# RingerPro.net
KiCad netlist of a schematic drawn in EAGLE
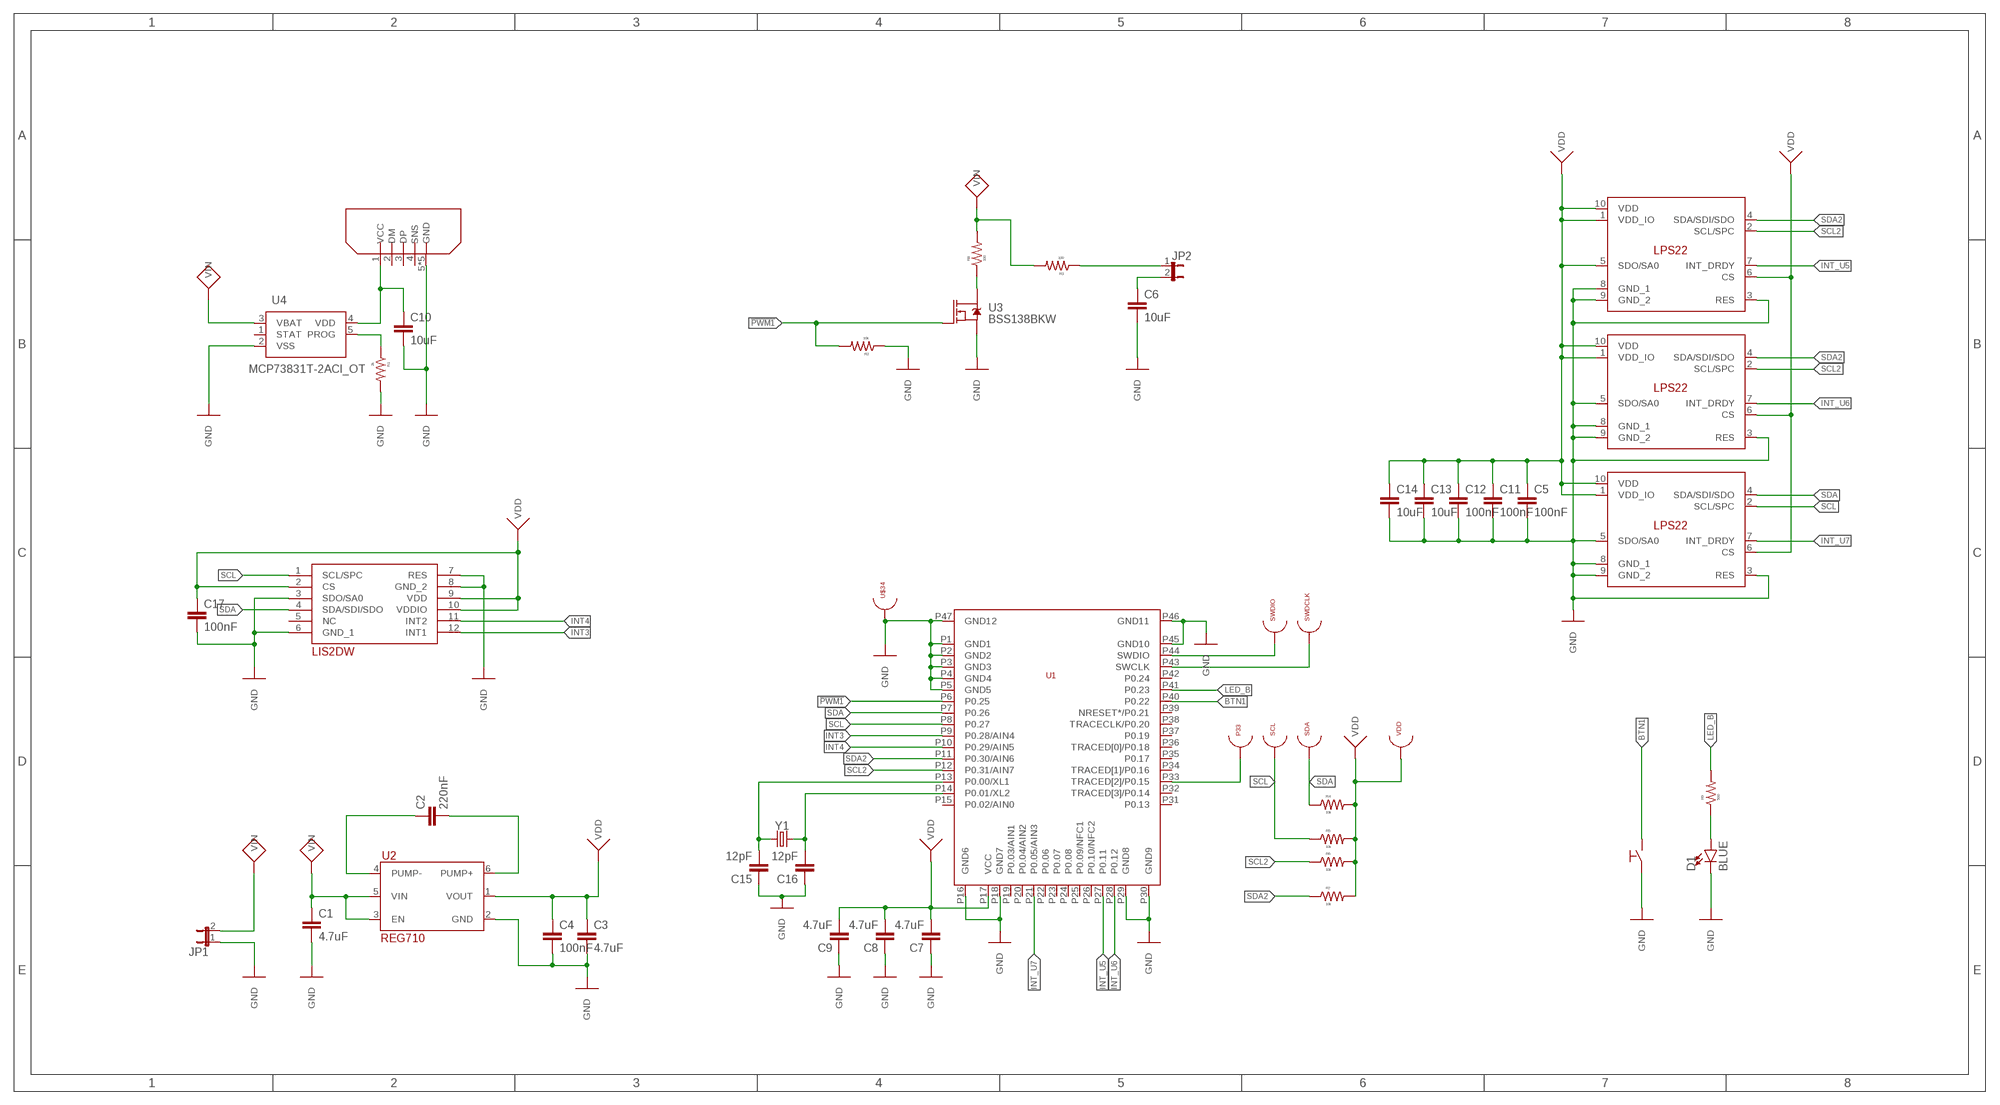
[diagram p0: schematic, sheet 1]

(export (version "E")
  (design (tool "Eeschema 10.0.6"))
  (components
    (comp (ref "C1")
      (value "4.7uF")
      (footprint "eagle-import:C0603")
      (libsource (lib "eagle-import") (part "CAPACITOR0603"))
    )
    (comp (ref "C2")
      (value "220nF")
      (footprint "eagle-import:C0603")
      (libsource (lib "eagle-import") (part "CAPACITOR0603"))
    )
    (comp (ref "C3")
      (value "4.7uF")
      (footprint "eagle-import:C0603")
      (libsource (lib "eagle-import") (part "CAPACITOR0603"))
    )
    (comp (ref "C4")
      (value "100nF")
      (footprint "eagle-import:C0603")
      (libsource (lib "eagle-import") (part "CAPACITOR0603"))
    )
    (comp (ref "C5")
      (value "100nF")
      (footprint "eagle-import:C0603")
      (libsource (lib "eagle-import") (part "CAPACITOR0603"))
    )
    (comp (ref "C6")
      (value "10uF")
      (footprint "eagle-import:C0603")
      (libsource (lib "eagle-import") (part "CAPACITOR0603"))
    )
    (comp (ref "C7")
      (value "4.7uF")
      (footprint "eagle-import:C0603")
      (libsource (lib "eagle-import") (part "CAPACITOR0603"))
    )
    (comp (ref "C8")
      (value "4.7uF")
      (footprint "eagle-import:C0603")
      (libsource (lib "eagle-import") (part "CAPACITOR0603"))
    )
    (comp (ref "C9")
      (value "4.7uF")
      (footprint "eagle-import:C0603")
      (libsource (lib "eagle-import") (part "CAPACITOR0603"))
    )
    (comp (ref "C10")
      (value "10uF")
      (footprint "eagle-import:C0603")
      (libsource (lib "eagle-import") (part "CAPACITOR0603"))
    )
    (comp (ref "C11")
      (value "100nF")
      (footprint "eagle-import:C0603")
      (libsource (lib "eagle-import") (part "CAPACITOR0603"))
    )
    (comp (ref "C12")
      (value "100nF")
      (footprint "eagle-import:C0603")
      (libsource (lib "eagle-import") (part "CAPACITOR0603"))
    )
    (comp (ref "C13")
      (value "10uF")
      (footprint "eagle-import:C0603")
      (libsource (lib "eagle-import") (part "CAPACITOR0603"))
    )
    (comp (ref "C14")
      (value "10uF")
      (footprint "eagle-import:C0603")
      (libsource (lib "eagle-import") (part "CAPACITOR0603"))
    )
    (comp (ref "C15")
      (value "12pF")
      (footprint "eagle-import:C0603")
      (libsource (lib "eagle-import") (part "CAPACITOR0603"))
    )
    (comp (ref "C16")
      (value "12pF")
      (footprint "eagle-import:C0603")
      (libsource (lib "eagle-import") (part "CAPACITOR0603"))
    )
    (comp (ref "C17")
      (value "100nF")
      (footprint "eagle-import:C0603")
      (libsource (lib "eagle-import") (part "CAPACITOR0603"))
    )
    (comp (ref "D1")
      (value "BLUE")
      (footprint "eagle-import:LED-0603")
      (libsource (lib "eagle-import") (part "LED-BLUE0603"))
    )
    (comp (ref "IC1")
      (value "LIS2DW12TR")
      (footprint "eagle-import:LGA-12")
      (fields (field (name "MOUSER_PART_NUMBER") "511-LIS2DW12TR"))
      (libsource (lib "eagle-import") (part "LIS2DW12TR"))
    )
    (comp (ref "JP1")
      (value "JP1E")
      (footprint "eagle-import:JP1")
      (libsource (lib "eagle-import") (part "JP1E"))
    )
    (comp (ref "JP2")
      (value "JP1E")
      (footprint "eagle-import:JP1")
      (libsource (lib "eagle-import") (part "JP1E"))
    )
    (comp (ref "P33")
      (value "TESTPOINT_22")
      (footprint "eagle-import:TESTPOINT_22")
      (libsource (lib "eagle-import") (part "TESTPOINT_22"))
    )
    (comp (ref "R1")
      (value "2k")
      (footprint "eagle-import:R0603")
      (libsource (lib "eagle-import") (part "RESISTOR0603"))
    )
    (comp (ref "R2")
      (value "10k")
      (footprint "eagle-import:R0603")
      (libsource (lib "eagle-import") (part "RESISTOR0603"))
    )
    (comp (ref "R3")
      (value "100")
      (footprint "eagle-import:R0603")
      (libsource (lib "eagle-import") (part "RESISTOR0603"))
    )
    (comp (ref "R4")
      (value "10k")
      (footprint "eagle-import:R0603")
      (libsource (lib "eagle-import") (part "RESISTOR0603"))
    )
    (comp (ref "R5")
      (value "10k")
      (footprint "eagle-import:R0603")
      (libsource (lib "eagle-import") (part "RESISTOR0603"))
    )
    (comp (ref "R6")
      (value "10k")
      (footprint "eagle-import:R0603")
      (libsource (lib "eagle-import") (part "RESISTOR0603"))
    )
    (comp (ref "R7")
      (value "10k")
      (footprint "eagle-import:R0603")
      (libsource (lib "eagle-import") (part "RESISTOR0603"))
    )
    (comp (ref "R8")
      (value "100")
      (footprint "eagle-import:R0603")
      (libsource (lib "eagle-import") (part "RESISTOR0603"))
    )
    (comp (ref "R9")
      (value "500")
      (footprint "eagle-import:R0603")
      (libsource (lib "eagle-import") (part "RESISTOR0603"))
    )
    (comp (ref "SCL")
      (value "TESTPOINT_22")
      (footprint "eagle-import:TESTPOINT_22")
      (libsource (lib "eagle-import") (part "TESTPOINT_22"))
    )
    (comp (ref "SDA")
      (value "TESTPOINT_22")
      (footprint "eagle-import:TESTPOINT_22")
      (libsource (lib "eagle-import") (part "TESTPOINT_22"))
    )
    (comp (ref "SPST1")
      (value "PTS526SK08")
      (footprint "eagle-import:PTS526SKG15SMTR2LFS")
      (libsource (lib "eagle-import") (part "PTS526SK08"))
    )
    (comp (ref "SWDCLK")
      (value "TESTPOINT_22")
      (footprint "eagle-import:TESTPOINT_22")
      (libsource (lib "eagle-import") (part "TESTPOINT_22"))
    )
    (comp (ref "SWDIO")
      (value "TESTPOINT_22")
      (footprint "eagle-import:TESTPOINT_22")
      (libsource (lib "eagle-import") (part "TESTPOINT_22"))
    )
    (comp (ref "U$23")
      (value "ZX80B5P")
      (footprint "eagle-import:ZX80B5P")
      (libsource (lib "eagle-import") (part "ZX80B5P"))
    )
    (comp (ref "U$34")
      (value "TESTPOINT_22")
      (footprint "eagle-import:TESTPOINT_22")
      (libsource (lib "eagle-import") (part "TESTPOINT_22"))
    )
    (comp (ref "U1")
      (value "BMD-300")
      (footprint "eagle-import:BMD-300")
      (libsource (lib "eagle-import") (part "BMD-300"))
    )
    (comp (ref "U2")
      (value "REG710")
      (footprint "eagle-import:SOT457")
      (libsource (lib "eagle-import") (part "REG710"))
    )
    (comp (ref "U3")
      (value "BSS138BKW")
      (footprint "eagle-import:SOT65P210X110-3N")
      (libsource (lib "eagle-import") (part "BSS138BKW"))
    )
    (comp (ref "U4")
      (value "MCP73831T-2ACI_OT")
      (footprint "eagle-import:SOT95P270X145-5N")
      (fields
        (field (name "MANUFACTURER_PART_NUMBER") "MCP73831T-2ACI/OT")
        (field (name "MOUSER_PART_NUMBER") "579-MCP73831T-2ACIOT")
      )
      (libsource (lib "eagle-import") (part "MCP73831T-2ACI_OT"))
    )
    (comp (ref "U5")
      (value "LPS22HBTR")
      (footprint "eagle-import:LPS22HDTR")
      (fields
        (field (name "MANUFACTURER_PART_NUMBER") "LPS22HDTR")
        (field (name "MOUSER_PART_NUMBER") "511-LPS22HDTR")
      )
      (libsource (lib "eagle-import") (part "LPS22HDTR"))
    )
    (comp (ref "U6")
      (value "LPS22HBTR")
      (footprint "eagle-import:LPS22HDTR")
      (fields
        (field (name "MANUFACTURER_PART_NUMBER") "LPS22HDTR")
        (field (name "MOUSER_PART_NUMBER") "511-LPS22HDTR")
      )
      (libsource (lib "eagle-import") (part "LPS22HDTR"))
    )
    (comp (ref "U7")
      (value "LPS22HBTR")
      (footprint "eagle-import:LPS22HDTR")
      (fields
        (field (name "MANUFACTURER_PART_NUMBER") "LPS22HDTR")
        (field (name "MOUSER_PART_NUMBER") "511-LPS22HDTR")
      )
      (libsource (lib "eagle-import") (part "LPS22HDTR"))
    )
    (comp (ref "VDD")
      (value "TESTPOINT_22")
      (footprint "eagle-import:TESTPOINT_22")
      (libsource (lib "eagle-import") (part "TESTPOINT_22"))
    )
    (comp (ref "Y1")
      (value "CRYSTALSMD-3.2X1.5")
      (footprint "eagle-import:CRYSTAL-SMD-3.2X1.5MM")
      (libsource (lib "eagle-import") (part "CRYSTALSMD-3.2X1.5"))
    )
  )
  (nets
    (net (code "1") (name "/~{PWM1}") (class "Default")
      (node (ref "R2") (pin "2") (pinfunction "2_2") (pintype "passive"))
      (node (ref "U1") (pin "P6") (pinfunction "P0.25_P6") (pintype "bidirectional"))
      (node (ref "U3") (pin "1") (pinfunction "G_1") (pintype "bidirectional"))
    )
    (net (code "2") (name "BTN1") (class "Default")
      (node (ref "SPST1") (pin "3") (pinfunction "P$2_3") (pintype "passive"))
      (node (ref "SPST1") (pin "4") (pinfunction "P$2_4") (pintype "passive"))
      (node (ref "U1") (pin "P40") (pinfunction "P0.22_P40") (pintype "bidirectional"))
    )
    (net (code "3") (name "GND") (class "Default")
      (node (ref "C1") (pin "2") (pinfunction "2_2") (pintype "passive"))
      (node (ref "C10") (pin "2") (pinfunction "2_2") (pintype "passive"))
      (node (ref "C11") (pin "2") (pinfunction "2_2") (pintype "passive"))
      (node (ref "C12") (pin "2") (pinfunction "2_2") (pintype "passive"))
      (node (ref "C13") (pin "2") (pinfunction "2_2") (pintype "passive"))
      (node (ref "C14") (pin "2") (pinfunction "2_2") (pintype "passive"))
      (node (ref "C15") (pin "1") (pinfunction "1_1") (pintype "passive"))
      (node (ref "C16") (pin "1") (pinfunction "1_1") (pintype "passive"))
      (node (ref "C17") (pin "2") (pinfunction "2_2") (pintype "passive"))
      (node (ref "C3") (pin "2") (pinfunction "2_2") (pintype "passive"))
      (node (ref "C4") (pin "2") (pinfunction "2_2") (pintype "passive"))
      (node (ref "C5") (pin "2") (pinfunction "2_2") (pintype "passive"))
      (node (ref "C6") (pin "2") (pinfunction "2_2") (pintype "passive"))
      (node (ref "C7") (pin "1") (pinfunction "1_1") (pintype "passive"))
      (node (ref "C8") (pin "1") (pinfunction "1_1") (pintype "passive"))
      (node (ref "C9") (pin "1") (pinfunction "1_1") (pintype "passive"))
      (node (ref "D1") (pin "C") (pinfunction "C_C") (pintype "passive"))
      (node (ref "IC1") (pin "3") (pinfunction "SDO/SA0_3") (pintype "bidirectional"))
      (node (ref "IC1") (pin "6") (pinfunction "GND_1_6") (pintype "bidirectional"))
      (node (ref "IC1") (pin "7") (pinfunction "RES_7") (pintype "bidirectional"))
      (node (ref "IC1") (pin "8") (pinfunction "GND_2_8") (pintype "bidirectional"))
      (node (ref "JP1") (pin "1") (pinfunction "1_1") (pintype "passive"))
      (node (ref "R1") (pin "2") (pinfunction "2_2") (pintype "passive"))
      (node (ref "R2") (pin "1") (pinfunction "1_1") (pintype "passive"))
      (node (ref "SPST1") (pin "1") (pinfunction "P$1_1") (pintype "passive"))
      (node (ref "SPST1") (pin "2") (pinfunction "P$1_2") (pintype "passive"))
      (node (ref "U$23") (pin "5") (pinfunction "GND_5") (pintype "bidirectional"))
      (node (ref "U$23") (pin "GND1") (pinfunction "GND_GND1") (pintype "bidirectional"))
      (node (ref "U$23") (pin "GND2") (pinfunction "GND_GND2") (pintype "bidirectional"))
      (node (ref "U$23") (pin "GND3") (pinfunction "GND_GND3") (pintype "bidirectional"))
      (node (ref "U$23") (pin "GND4") (pinfunction "GND_GND4") (pintype "bidirectional"))
      (node (ref "U$34") (pin "P$1") (pinfunction "P$1_P$1") (pintype "bidirectional"))
      (node (ref "U1") (pin "P1") (pinfunction "GND1_P1") (pintype "bidirectional"))
      (node (ref "U1") (pin "P16") (pinfunction "GND6_P16") (pintype "bidirectional"))
      (node (ref "U1") (pin "P18") (pinfunction "GND7_P18") (pintype "bidirectional"))
      (node (ref "U1") (pin "P2") (pinfunction "GND2_P2") (pintype "bidirectional"))
      (node (ref "U1") (pin "P29") (pinfunction "GND8_P29") (pintype "bidirectional"))
      (node (ref "U1") (pin "P3") (pinfunction "GND3_P3") (pintype "bidirectional"))
      (node (ref "U1") (pin "P30") (pinfunction "GND9_P30") (pintype "bidirectional"))
      (node (ref "U1") (pin "P4") (pinfunction "GND4_P4") (pintype "bidirectional"))
      (node (ref "U1") (pin "P45") (pinfunction "GND10_P45") (pintype "bidirectional"))
      (node (ref "U1") (pin "P46") (pinfunction "GND11_P46") (pintype "bidirectional"))
      (node (ref "U1") (pin "P47") (pinfunction "GND12_P47") (pintype "bidirectional"))
      (node (ref "U1") (pin "P5") (pinfunction "GND5_P5") (pintype "bidirectional"))
      (node (ref "U2") (pin "2") (pinfunction "GND_2") (pintype "bidirectional"))
      (node (ref "U3") (pin "2") (pinfunction "S_2") (pintype "bidirectional"))
      (node (ref "U4") (pin "2") (pinfunction "VSS_2") (pintype "bidirectional"))
      (node (ref "U5") (pin "3") (pinfunction "RES_3") (pintype "bidirectional"))
      (node (ref "U5") (pin "8") (pinfunction "GND_1_8") (pintype "bidirectional"))
      (node (ref "U5") (pin "9") (pinfunction "GND_2_9") (pintype "bidirectional"))
      (node (ref "U6") (pin "3") (pinfunction "RES_3") (pintype "bidirectional"))
      (node (ref "U6") (pin "5") (pinfunction "SDO/SA0_5") (pintype "bidirectional"))
      (node (ref "U6") (pin "8") (pinfunction "GND_1_8") (pintype "bidirectional"))
      (node (ref "U6") (pin "9") (pinfunction "GND_2_9") (pintype "bidirectional"))
      (node (ref "U7") (pin "3") (pinfunction "RES_3") (pintype "bidirectional"))
      (node (ref "U7") (pin "5") (pinfunction "SDO/SA0_5") (pintype "bidirectional"))
      (node (ref "U7") (pin "8") (pinfunction "GND_1_8") (pintype "bidirectional"))
      (node (ref "U7") (pin "9") (pinfunction "GND_2_9") (pintype "bidirectional"))
    )
    (net (code "4") (name "INT3") (class "Default")
      (node (ref "IC1") (pin "12") (pinfunction "INT1_12") (pintype "bidirectional"))
      (node (ref "U1") (pin "P9") (pinfunction "P0.28/AIN4_P9") (pintype "bidirectional"))
    )
    (net (code "5") (name "INT4") (class "Default")
      (node (ref "IC1") (pin "11") (pinfunction "INT2_11") (pintype "bidirectional"))
      (node (ref "U1") (pin "P10") (pinfunction "P0.29/AIN5_P10") (pintype "bidirectional"))
    )
    (net (code "6") (name "INT_U5") (class "Default")
      (node (ref "U1") (pin "P27") (pinfunction "P0.11_P27") (pintype "bidirectional"))
      (node (ref "U5") (pin "7") (pinfunction "INT_DRDY_7") (pintype "bidirectional"))
    )
    (net (code "7") (name "INT_U6") (class "Default")
      (node (ref "U1") (pin "P28") (pinfunction "P0.12_P28") (pintype "bidirectional"))
      (node (ref "U6") (pin "7") (pinfunction "INT_DRDY_7") (pintype "bidirectional"))
    )
    (net (code "8") (name "INT_U7") (class "Default")
      (node (ref "U1") (pin "P21") (pinfunction "P0.05/AIN3_P21") (pintype "bidirectional"))
      (node (ref "U7") (pin "7") (pinfunction "INT_DRDY_7") (pintype "bidirectional"))
    )
    (net (code "9") (name "LED_B") (class "Default")
      (node (ref "R9") (pin "2") (pinfunction "2_2") (pintype "passive"))
      (node (ref "U1") (pin "P41") (pinfunction "P0.23_P41") (pintype "bidirectional"))
    )
    (net (code "10") (name "Net-(C6-Pad1)") (class "Default")
      (node (ref "C6") (pin "1") (pinfunction "1_1") (pintype "passive"))
      (node (ref "JP2") (pin "2") (pinfunction "2_2") (pintype "passive"))
    )
    (net (code "11") (name "Net-(D1-PadA)") (class "Default")
      (node (ref "D1") (pin "A") (pinfunction "A_A") (pintype "passive"))
      (node (ref "R9") (pin "1") (pinfunction "1_1") (pintype "passive"))
    )
    (net (code "12") (name "Net-(JP2-Pad1)") (class "Default")
      (node (ref "JP2") (pin "1") (pinfunction "1_1") (pintype "passive"))
      (node (ref "R3") (pin "1") (pinfunction "1_1") (pintype "passive"))
    )
    (net (code "13") (name "Net-(U$23-VCC)") (class "Default")
      (node (ref "C10") (pin "1") (pinfunction "1_1") (pintype "passive"))
      (node (ref "U$23") (pin "1") (pinfunction "VCC_1") (pintype "bidirectional"))
      (node (ref "U4") (pin "4") (pinfunction "VDD_4") (pintype "bidirectional"))
    )
    (net (code "14") (name "Net-(U1-P0.00{slash}XL1)") (class "Default")
      (node (ref "C15") (pin "2") (pinfunction "2_2") (pintype "passive"))
      (node (ref "U1") (pin "P13") (pinfunction "P0.00/XL1_P13") (pintype "bidirectional"))
      (node (ref "Y1") (pin "P$1") (pinfunction "1_P$1") (pintype "passive"))
    )
    (net (code "15") (name "Net-(U1-P0.01{slash}XL2)") (class "Default")
      (node (ref "C16") (pin "2") (pinfunction "2_2") (pintype "passive"))
      (node (ref "U1") (pin "P14") (pinfunction "P0.01/XL2_P14") (pintype "bidirectional"))
      (node (ref "Y1") (pin "P$2") (pinfunction "2_P$2") (pintype "passive"))
    )
    (net (code "16") (name "Net-(U1-SWCLK)") (class "Default")
      (node (ref "SWDCLK") (pin "P$1") (pinfunction "P$1_P$1") (pintype "bidirectional"))
      (node (ref "U1") (pin "P43") (pinfunction "SWCLK_P43") (pintype "bidirectional"))
    )
    (net (code "17") (name "Net-(U1-SWDIO)") (class "Default")
      (node (ref "SWDIO") (pin "P$1") (pinfunction "P$1_P$1") (pintype "bidirectional"))
      (node (ref "U1") (pin "P44") (pinfunction "SWDIO_P44") (pintype "bidirectional"))
    )
    (net (code "18") (name "Net-(U1-TRACED[2]{slash}P0.15)") (class "Default")
      (node (ref "P33") (pin "P$1") (pinfunction "P$1_P$1") (pintype "bidirectional"))
      (node (ref "U1") (pin "P33") (pinfunction "TRACED[2]/P0.15_P33") (pintype "bidirectional"))
    )
    (net (code "19") (name "Net-(U2-PUMP+)") (class "Default")
      (node (ref "C2") (pin "2") (pinfunction "2_2") (pintype "passive"))
      (node (ref "U2") (pin "6") (pinfunction "PUMP+_6") (pintype "bidirectional"))
    )
    (net (code "20") (name "Net-(U2-PUMP-)") (class "Default")
      (node (ref "C2") (pin "1") (pinfunction "1_1") (pintype "passive"))
      (node (ref "U2") (pin "4") (pinfunction "PUMP-_4") (pintype "bidirectional"))
    )
    (net (code "21") (name "Net-(U3-D)") (class "Default")
      (node (ref "R8") (pin "1") (pinfunction "1_1") (pintype "passive"))
      (node (ref "U3") (pin "3") (pinfunction "D_3") (pintype "bidirectional"))
    )
    (net (code "22") (name "Net-(U4-PROG)") (class "Default")
      (node (ref "R1") (pin "1") (pinfunction "1_1") (pintype "passive"))
      (node (ref "U4") (pin "5") (pinfunction "PROG_5") (pintype "bidirectional"))
    )
    (net (code "23") (name "SCL") (class "Default")
      (node (ref "IC1") (pin "1") (pinfunction "SCL/SPC_1") (pintype "bidirectional"))
      (node (ref "R5") (pin "1") (pinfunction "1_1") (pintype "passive"))
      (node (ref "SCL") (pin "P$1") (pinfunction "P$1_P$1") (pintype "bidirectional"))
      (node (ref "U1") (pin "P8") (pinfunction "P0.27_P8") (pintype "bidirectional"))
      (node (ref "U7") (pin "2") (pinfunction "SCL/SPC_2") (pintype "bidirectional"))
    )
    (net (code "24") (name "SCL2") (class "Default")
      (node (ref "R6") (pin "1") (pinfunction "1_1") (pintype "passive"))
      (node (ref "U1") (pin "P12") (pinfunction "P0.31/AIN7_P12") (pintype "bidirectional"))
      (node (ref "U5") (pin "2") (pinfunction "SCL/SPC_2") (pintype "bidirectional"))
      (node (ref "U6") (pin "2") (pinfunction "SCL/SPC_2") (pintype "bidirectional"))
    )
    (net (code "25") (name "SDA") (class "Default")
      (node (ref "IC1") (pin "4") (pinfunction "SDA/SDI/SDO_4") (pintype "bidirectional"))
      (node (ref "R4") (pin "1") (pinfunction "1_1") (pintype "passive"))
      (node (ref "SDA") (pin "P$1") (pinfunction "P$1_P$1") (pintype "bidirectional"))
      (node (ref "U1") (pin "P7") (pinfunction "P0.26_P7") (pintype "bidirectional"))
      (node (ref "U7") (pin "4") (pinfunction "SDA/SDI/SDO_4") (pintype "bidirectional"))
    )
    (net (code "26") (name "SDA2") (class "Default")
      (node (ref "R7") (pin "1") (pinfunction "1_1") (pintype "passive"))
      (node (ref "U1") (pin "P11") (pinfunction "P0.30/AIN6_P11") (pintype "bidirectional"))
      (node (ref "U5") (pin "4") (pinfunction "SDA/SDI/SDO_4") (pintype "bidirectional"))
      (node (ref "U6") (pin "4") (pinfunction "SDA/SDI/SDO_4") (pintype "bidirectional"))
    )
    (net (code "27") (name "VDD") (class "Default")
      (node (ref "C11") (pin "1") (pinfunction "1_1") (pintype "passive"))
      (node (ref "C12") (pin "1") (pinfunction "1_1") (pintype "passive"))
      (node (ref "C13") (pin "1") (pinfunction "1_1") (pintype "passive"))
      (node (ref "C14") (pin "1") (pinfunction "1_1") (pintype "passive"))
      (node (ref "C17") (pin "1") (pinfunction "1_1") (pintype "passive"))
      (node (ref "C3") (pin "1") (pinfunction "1_1") (pintype "passive"))
      (node (ref "C4") (pin "1") (pinfunction "1_1") (pintype "passive"))
      (node (ref "C5") (pin "1") (pinfunction "1_1") (pintype "passive"))
      (node (ref "C7") (pin "2") (pinfunction "2_2") (pintype "passive"))
      (node (ref "C8") (pin "2") (pinfunction "2_2") (pintype "passive"))
      (node (ref "C9") (pin "2") (pinfunction "2_2") (pintype "passive"))
      (node (ref "IC1") (pin "10") (pinfunction "VDDIO_10") (pintype "bidirectional"))
      (node (ref "IC1") (pin "2") (pinfunction "CS_2") (pintype "bidirectional"))
      (node (ref "IC1") (pin "9") (pinfunction "VDD_9") (pintype "bidirectional"))
      (node (ref "R4") (pin "2") (pinfunction "2_2") (pintype "passive"))
      (node (ref "R5") (pin "2") (pinfunction "2_2") (pintype "passive"))
      (node (ref "R6") (pin "2") (pinfunction "2_2") (pintype "passive"))
      (node (ref "R7") (pin "2") (pinfunction "2_2") (pintype "passive"))
      (node (ref "U1") (pin "P17") (pinfunction "VCC_P17") (pintype "bidirectional"))
      (node (ref "U2") (pin "1") (pinfunction "VOUT_1") (pintype "bidirectional"))
      (node (ref "U5") (pin "1") (pinfunction "VDD_IO_1") (pintype "bidirectional"))
      (node (ref "U5") (pin "10") (pinfunction "VDD_10") (pintype "bidirectional"))
      (node (ref "U5") (pin "5") (pinfunction "SDO/SA0_5") (pintype "bidirectional"))
      (node (ref "U5") (pin "6") (pinfunction "CS_6") (pintype "bidirectional"))
      (node (ref "U6") (pin "1") (pinfunction "VDD_IO_1") (pintype "bidirectional"))
      (node (ref "U6") (pin "10") (pinfunction "VDD_10") (pintype "bidirectional"))
      (node (ref "U6") (pin "6") (pinfunction "CS_6") (pintype "bidirectional"))
      (node (ref "U7") (pin "1") (pinfunction "VDD_IO_1") (pintype "bidirectional"))
      (node (ref "U7") (pin "10") (pinfunction "VDD_10") (pintype "bidirectional"))
      (node (ref "U7") (pin "6") (pinfunction "CS_6") (pintype "bidirectional"))
      (node (ref "VDD") (pin "P$1") (pinfunction "P$1_P$1") (pintype "bidirectional"))
    )
    (net (code "28") (name "VIN") (class "Default")
      (node (ref "C1") (pin "1") (pinfunction "1_1") (pintype "passive"))
      (node (ref "JP1") (pin "2") (pinfunction "2_2") (pintype "passive"))
      (node (ref "R3") (pin "2") (pinfunction "2_2") (pintype "passive"))
      (node (ref "R8") (pin "2") (pinfunction "2_2") (pintype "passive"))
      (node (ref "U2") (pin "3") (pinfunction "EN_3") (pintype "bidirectional"))
      (node (ref "U2") (pin "5") (pinfunction "VIN_5") (pintype "bidirectional"))
      (node (ref "U4") (pin "3") (pinfunction "VBAT_3") (pintype "bidirectional"))
    )
    (net (code "29") (name "unconnected-(IC1-NC-Pad5)") (class "Default")
      (node (ref "IC1") (pin "5") (pinfunction "NC_5") (pintype "no_connect"))
    )
    (net (code "30") (name "unconnected-(U$23-DM-Pad2)") (class "Default")
      (node (ref "U$23") (pin "2") (pinfunction "DM_2") (pintype "bidirectional"))
    )
    (net (code "31") (name "unconnected-(U$23-DP-Pad3)") (class "Default")
      (node (ref "U$23") (pin "3") (pinfunction "DP_3") (pintype "bidirectional"))
    )
    (net (code "32") (name "unconnected-(U$23-SNS-Pad4)") (class "Default")
      (node (ref "U$23") (pin "4") (pinfunction "SNS_4") (pintype "bidirectional"))
    )
    (net (code "33") (name "unconnected-(U1-NRESET*{slash}P0.21-PadP39)") (class "Default")
      (node (ref "U1") (pin "P39") (pinfunction "NRESET*/P0.21_P39") (pintype "bidirectional"))
    )
    (net (code "34") (name "unconnected-(U1-P0.02{slash}AIN0-PadP15)") (class "Default")
      (node (ref "U1") (pin "P15") (pinfunction "P0.02/AIN0_P15") (pintype "bidirectional"))
    )
    (net (code "35") (name "unconnected-(U1-P0.03{slash}AIN1-PadP19)") (class "Default")
      (node (ref "U1") (pin "P19") (pinfunction "P0.03/AIN1_P19") (pintype "bidirectional"))
    )
    (net (code "36") (name "unconnected-(U1-P0.04{slash}AIN2-PadP20)") (class "Default")
      (node (ref "U1") (pin "P20") (pinfunction "P0.04/AIN2_P20") (pintype "bidirectional"))
    )
    (net (code "37") (name "unconnected-(U1-P0.06-PadP22)") (class "Default")
      (node (ref "U1") (pin "P22") (pinfunction "P0.06_P22") (pintype "bidirectional"))
    )
    (net (code "38") (name "unconnected-(U1-P0.07-PadP23)") (class "Default")
      (node (ref "U1") (pin "P23") (pinfunction "P0.07_P23") (pintype "bidirectional"))
    )
    (net (code "39") (name "unconnected-(U1-P0.08-PadP24)") (class "Default")
      (node (ref "U1") (pin "P24") (pinfunction "P0.08_P24") (pintype "bidirectional"))
    )
    (net (code "40") (name "unconnected-(U1-P0.09{slash}NFC1-PadP25)") (class "Default")
      (node (ref "U1") (pin "P25") (pinfunction "P0.09/NFC1_P25") (pintype "bidirectional"))
    )
    (net (code "41") (name "unconnected-(U1-P0.10{slash}NFC2-PadP26)") (class "Default")
      (node (ref "U1") (pin "P26") (pinfunction "P0.10/NFC2_P26") (pintype "bidirectional"))
    )
    (net (code "42") (name "unconnected-(U1-P0.13-PadP31)") (class "Default")
      (node (ref "U1") (pin "P31") (pinfunction "P0.13_P31") (pintype "bidirectional"))
    )
    (net (code "43") (name "unconnected-(U1-P0.17-PadP35)") (class "Default")
      (node (ref "U1") (pin "P35") (pinfunction "P0.17_P35") (pintype "bidirectional"))
    )
    (net (code "44") (name "unconnected-(U1-P0.19-PadP37)") (class "Default")
      (node (ref "U1") (pin "P37") (pinfunction "P0.19_P37") (pintype "bidirectional"))
    )
    (net (code "45") (name "unconnected-(U1-P0.24-PadP42)") (class "Default")
      (node (ref "U1") (pin "P42") (pinfunction "P0.24_P42") (pintype "bidirectional"))
    )
    (net (code "46") (name "unconnected-(U1-TRACECLK{slash}P0.20-PadP38)") (class "Default")
      (node (ref "U1") (pin "P38") (pinfunction "TRACECLK/P0.20_P38") (pintype "bidirectional"))
    )
    (net (code "47") (name "unconnected-(U1-TRACED[0]{slash}P0.18-PadP36)") (class "Default")
      (node (ref "U1") (pin "P36") (pinfunction "TRACED[0]/P0.18_P36") (pintype "bidirectional"))
    )
    (net (code "48") (name "unconnected-(U1-TRACED[1]{slash}P0.16-PadP34)") (class "Default")
      (node (ref "U1") (pin "P34") (pinfunction "TRACED[1]/P0.16_P34") (pintype "bidirectional"))
    )
    (net (code "49") (name "unconnected-(U1-TRACED[3]{slash}P0.14-PadP32)") (class "Default")
      (node (ref "U1") (pin "P32") (pinfunction "TRACED[3]/P0.14_P32") (pintype "bidirectional"))
    )
    (net (code "50") (name "unconnected-(U4-STAT-Pad1)") (class "Default")
      (node (ref "U4") (pin "1") (pinfunction "STAT_1") (pintype "bidirectional"))
    )
  )
)
